# Primavera.net
KiCad netlist of a schematic drawn in Altium Designer
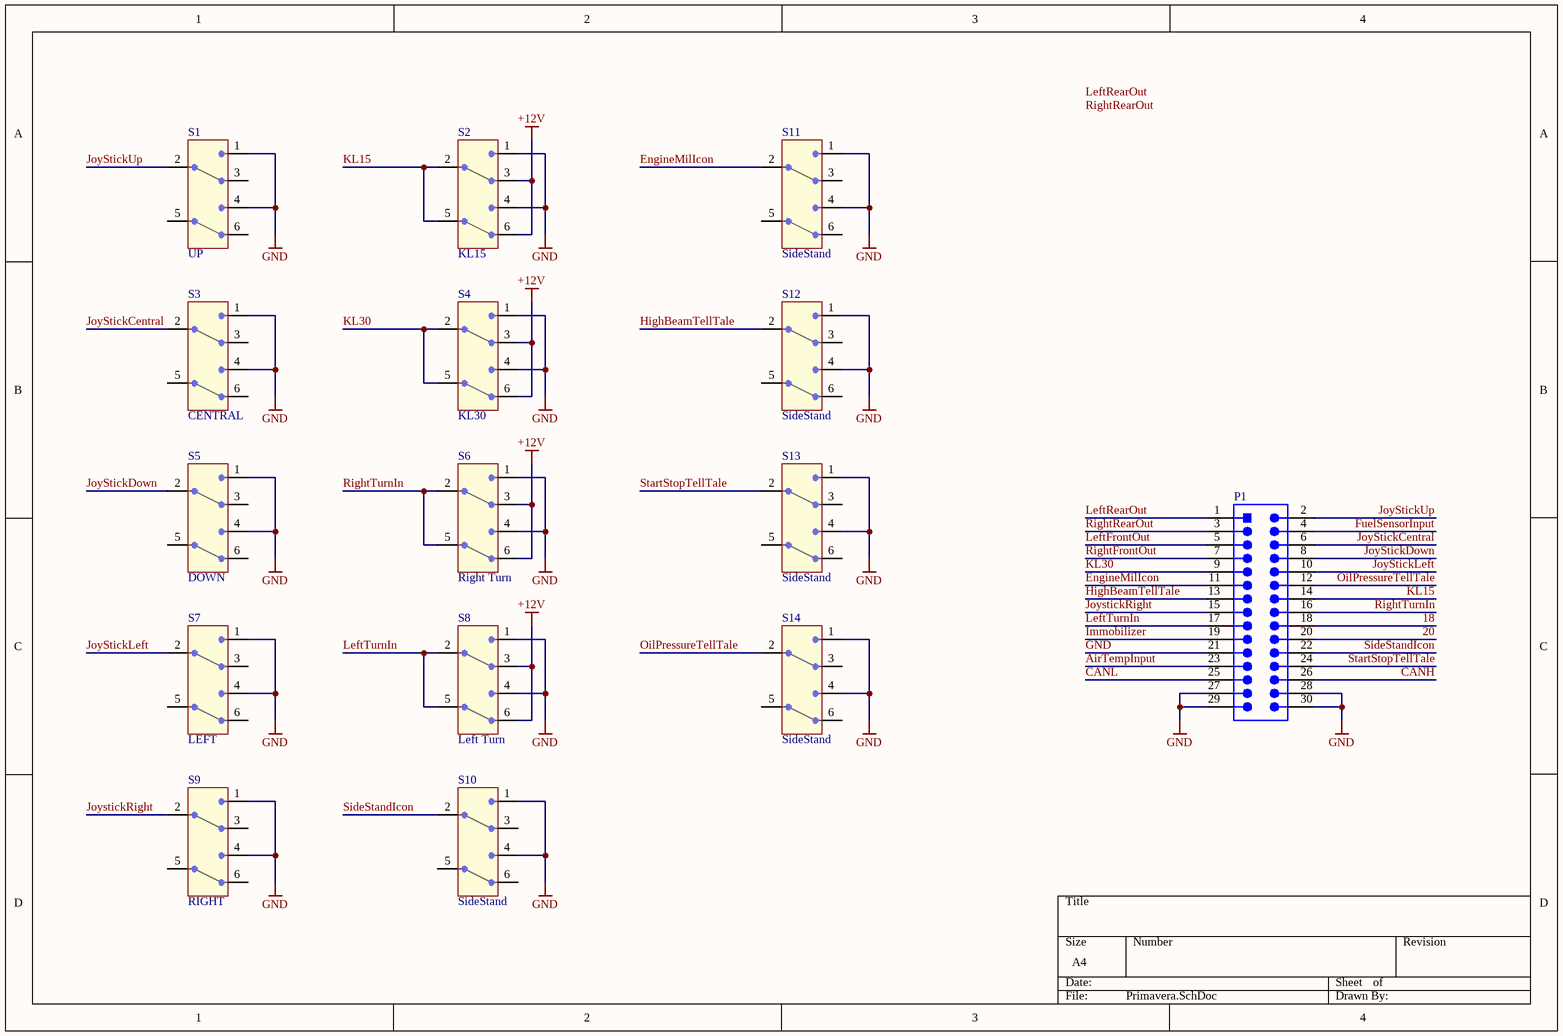
[diagram p0: Primavera.SchDoc]

(export (version "E")
  (design (tool "Eeschema 10.0.6"))
  (components
    (comp (ref "P1")
      (value "_30")
      (footprint "61203421721 - 30pole")
      (description "WR-BHD Box Header with short lever, Male, pitch 2.54mm, THT, Right Angle, 30p")
      (fields
        (field (name "MANUFACTURER") "Wurth Elektronik")
        (field (name "MANUFACTURER PART NUMBER") "61202622121")
      )
      (libsource (lib "Altium_WR-BHD (rev22a)") (part "61202622121_30"))
    )
    (comp (ref "S1")
      (value "UP")
      (footprint "8.5x8.5_DPDT")
      (libsource (lib "Switches") (part "8.5x8.5_DPDT"))
    )
    (comp (ref "S2")
      (value "KL15")
      (footprint "8.5x8.5_DPDT")
      (libsource (lib "Switches") (part "8.5x8.5_DPDT"))
    )
    (comp (ref "S3")
      (value "CENTRAL")
      (footprint "8.5x8.5_DPDT")
      (libsource (lib "Switches") (part "8.5x8.5_DPDT"))
    )
    (comp (ref "S4")
      (value "KL30")
      (footprint "8.5x8.5_DPDT")
      (libsource (lib "Switches") (part "8.5x8.5_DPDT"))
    )
    (comp (ref "S5")
      (value "DOWN")
      (footprint "8.5x8.5_DPDT")
      (libsource (lib "Switches") (part "8.5x8.5_DPDT"))
    )
    (comp (ref "S6")
      (value "Right Turn")
      (footprint "8.5x8.5_DPDT")
      (libsource (lib "Switches") (part "8.5x8.5_DPDT"))
    )
    (comp (ref "S7")
      (value "LEFT")
      (footprint "8.5x8.5_DPDT")
      (libsource (lib "Switches") (part "8.5x8.5_DPDT"))
    )
    (comp (ref "S8")
      (value "Left Turn")
      (footprint "8.5x8.5_DPDT")
      (libsource (lib "Switches") (part "8.5x8.5_DPDT"))
    )
    (comp (ref "S9")
      (value "RIGHT")
      (footprint "8.5x8.5_DPDT")
      (libsource (lib "Switches") (part "8.5x8.5_DPDT"))
    )
    (comp (ref "S10")
      (value "SideStand")
      (footprint "8.5x8.5_DPDT")
      (libsource (lib "Switches") (part "8.5x8.5_DPDT"))
    )
    (comp (ref "S11")
      (value "SideStand")
      (footprint "8.5x8.5_DPDT")
      (libsource (lib "Switches") (part "8.5x8.5_DPDT"))
    )
    (comp (ref "S12")
      (value "SideStand")
      (footprint "8.5x8.5_DPDT")
      (libsource (lib "Switches") (part "8.5x8.5_DPDT"))
    )
    (comp (ref "S13")
      (value "SideStand")
      (footprint "8.5x8.5_DPDT")
      (libsource (lib "Switches") (part "8.5x8.5_DPDT"))
    )
    (comp (ref "S14")
      (value "SideStand")
      (footprint "8.5x8.5_DPDT")
      (libsource (lib "Switches") (part "8.5x8.5_DPDT"))
    )
  )
  (nets
    (net (code "1") (name "+12V") (class "Default")
      (node (ref "S2") (pin "3") (pinfunction "3_3") (pintype "passive"))
      (node (ref "S2") (pin "6") (pinfunction "6_6") (pintype "passive"))
      (node (ref "S4") (pin "3") (pinfunction "3_3") (pintype "passive"))
      (node (ref "S4") (pin "6") (pinfunction "6_6") (pintype "passive"))
      (node (ref "S6") (pin "3") (pinfunction "3_3") (pintype "passive"))
      (node (ref "S6") (pin "6") (pinfunction "6_6") (pintype "passive"))
      (node (ref "S8") (pin "3") (pinfunction "3_3") (pintype "passive"))
      (node (ref "S8") (pin "6") (pinfunction "6_6") (pintype "passive"))
    )
    (net (code "2") (name "/18") (class "Default")
      (node (ref "P1") (pin "18") (pinfunction "18_18") (pintype "passive"))
    )
    (net (code "3") (name "/20") (class "Default")
      (node (ref "P1") (pin "20") (pinfunction "20_20") (pintype "passive"))
    )
    (net (code "4") (name "/AirTempInput") (class "Default")
      (node (ref "P1") (pin "23") (pinfunction "23_23") (pintype "passive"))
    )
    (net (code "5") (name "/CANH") (class "Default")
      (node (ref "P1") (pin "26") (pinfunction "26_26") (pintype "passive"))
    )
    (net (code "6") (name "/CANL") (class "Default")
      (node (ref "P1") (pin "25") (pinfunction "25_25") (pintype "passive"))
    )
    (net (code "7") (name "/EngineMilIcon") (class "Default")
      (node (ref "P1") (pin "11") (pinfunction "11_11") (pintype "passive"))
      (node (ref "S11") (pin "2") (pinfunction "2_2") (pintype "passive"))
    )
    (net (code "8") (name "/FuelSensorInput") (class "Default")
      (node (ref "P1") (pin "4") (pinfunction "4_4") (pintype "passive"))
    )
    (net (code "9") (name "/HighBeamTellTale") (class "Default")
      (node (ref "P1") (pin "13") (pinfunction "13_13") (pintype "passive"))
      (node (ref "S12") (pin "2") (pinfunction "2_2") (pintype "passive"))
    )
    (net (code "10") (name "/Immobilizer") (class "Default")
      (node (ref "P1") (pin "19") (pinfunction "19_19") (pintype "passive"))
    )
    (net (code "11") (name "/JoyStickCentral") (class "Default")
      (node (ref "P1") (pin "6") (pinfunction "6_6") (pintype "passive"))
      (node (ref "S3") (pin "2") (pinfunction "2_2") (pintype "passive"))
    )
    (net (code "12") (name "/JoyStickDown") (class "Default")
      (node (ref "P1") (pin "8") (pinfunction "8_8") (pintype "passive"))
      (node (ref "S5") (pin "2") (pinfunction "2_2") (pintype "passive"))
    )
    (net (code "13") (name "/JoyStickLeft") (class "Default")
      (node (ref "P1") (pin "10") (pinfunction "10_10") (pintype "passive"))
      (node (ref "S7") (pin "2") (pinfunction "2_2") (pintype "passive"))
    )
    (net (code "14") (name "/JoyStickUp") (class "Default")
      (node (ref "P1") (pin "2") (pinfunction "2_2") (pintype "passive"))
      (node (ref "S1") (pin "2") (pinfunction "2_2") (pintype "passive"))
    )
    (net (code "15") (name "/JoystickRight") (class "Default")
      (node (ref "P1") (pin "15") (pinfunction "15_15") (pintype "passive"))
      (node (ref "S9") (pin "2") (pinfunction "2_2") (pintype "passive"))
    )
    (net (code "16") (name "/KL15") (class "Default")
      (node (ref "P1") (pin "14") (pinfunction "14_14") (pintype "passive"))
      (node (ref "S2") (pin "2") (pinfunction "2_2") (pintype "passive"))
      (node (ref "S2") (pin "5") (pinfunction "5_5") (pintype "passive"))
    )
    (net (code "17") (name "/KL30") (class "Default")
      (node (ref "P1") (pin "9") (pinfunction "9_9") (pintype "passive"))
      (node (ref "S4") (pin "2") (pinfunction "2_2") (pintype "passive"))
      (node (ref "S4") (pin "5") (pinfunction "5_5") (pintype "passive"))
    )
    (net (code "18") (name "/LeftFrontOut") (class "Default")
      (node (ref "P1") (pin "5") (pinfunction "5_5") (pintype "passive"))
    )
    (net (code "19") (name "/LeftRearOut") (class "Default")
      (node (ref "P1") (pin "1") (pinfunction "1_1") (pintype "passive"))
    )
    (net (code "20") (name "/LeftTurnIn") (class "Default")
      (node (ref "P1") (pin "17") (pinfunction "17_17") (pintype "passive"))
      (node (ref "S8") (pin "2") (pinfunction "2_2") (pintype "passive"))
      (node (ref "S8") (pin "5") (pinfunction "5_5") (pintype "passive"))
    )
    (net (code "21") (name "/OilPressureTellTale") (class "Default")
      (node (ref "P1") (pin "12") (pinfunction "12_12") (pintype "passive"))
      (node (ref "S14") (pin "2") (pinfunction "2_2") (pintype "passive"))
    )
    (net (code "22") (name "/RightFrontOut") (class "Default")
      (node (ref "P1") (pin "7") (pinfunction "7_7") (pintype "passive"))
    )
    (net (code "23") (name "/RightRearOut") (class "Default")
      (node (ref "P1") (pin "3") (pinfunction "3_3") (pintype "passive"))
    )
    (net (code "24") (name "/RightTurnIn") (class "Default")
      (node (ref "P1") (pin "16") (pinfunction "16_16") (pintype "passive"))
      (node (ref "S6") (pin "2") (pinfunction "2_2") (pintype "passive"))
      (node (ref "S6") (pin "5") (pinfunction "5_5") (pintype "passive"))
    )
    (net (code "25") (name "/SideStandIcon") (class "Default")
      (node (ref "P1") (pin "22") (pinfunction "22_22") (pintype "passive"))
      (node (ref "S10") (pin "2") (pinfunction "2_2") (pintype "passive"))
    )
    (net (code "26") (name "/StartStopTellTale") (class "Default")
      (node (ref "P1") (pin "24") (pinfunction "24_24") (pintype "passive"))
      (node (ref "S13") (pin "2") (pinfunction "2_2") (pintype "passive"))
    )
    (net (code "27") (name "GND") (class "Default")
      (node (ref "P1") (pin "21") (pinfunction "21_21") (pintype "passive"))
      (node (ref "P1") (pin "27") (pinfunction "27_27") (pintype "passive"))
      (node (ref "P1") (pin "28") (pinfunction "28_28") (pintype "passive"))
      (node (ref "P1") (pin "29") (pinfunction "29_29") (pintype "passive"))
      (node (ref "P1") (pin "30") (pinfunction "30_30") (pintype "passive"))
      (node (ref "S1") (pin "1") (pinfunction "1_1") (pintype "passive"))
      (node (ref "S1") (pin "4") (pinfunction "4_4") (pintype "passive"))
      (node (ref "S10") (pin "1") (pinfunction "1_1") (pintype "passive"))
      (node (ref "S10") (pin "4") (pinfunction "4_4") (pintype "passive"))
      (node (ref "S11") (pin "1") (pinfunction "1_1") (pintype "passive"))
      (node (ref "S11") (pin "4") (pinfunction "4_4") (pintype "passive"))
      (node (ref "S12") (pin "1") (pinfunction "1_1") (pintype "passive"))
      (node (ref "S12") (pin "4") (pinfunction "4_4") (pintype "passive"))
      (node (ref "S13") (pin "1") (pinfunction "1_1") (pintype "passive"))
      (node (ref "S13") (pin "4") (pinfunction "4_4") (pintype "passive"))
      (node (ref "S14") (pin "1") (pinfunction "1_1") (pintype "passive"))
      (node (ref "S14") (pin "4") (pinfunction "4_4") (pintype "passive"))
      (node (ref "S2") (pin "1") (pinfunction "1_1") (pintype "passive"))
      (node (ref "S2") (pin "4") (pinfunction "4_4") (pintype "passive"))
      (node (ref "S3") (pin "1") (pinfunction "1_1") (pintype "passive"))
      (node (ref "S3") (pin "4") (pinfunction "4_4") (pintype "passive"))
      (node (ref "S4") (pin "1") (pinfunction "1_1") (pintype "passive"))
      (node (ref "S4") (pin "4") (pinfunction "4_4") (pintype "passive"))
      (node (ref "S5") (pin "1") (pinfunction "1_1") (pintype "passive"))
      (node (ref "S5") (pin "4") (pinfunction "4_4") (pintype "passive"))
      (node (ref "S6") (pin "1") (pinfunction "1_1") (pintype "passive"))
      (node (ref "S6") (pin "4") (pinfunction "4_4") (pintype "passive"))
      (node (ref "S7") (pin "1") (pinfunction "1_1") (pintype "passive"))
      (node (ref "S7") (pin "4") (pinfunction "4_4") (pintype "passive"))
      (node (ref "S8") (pin "1") (pinfunction "1_1") (pintype "passive"))
      (node (ref "S8") (pin "4") (pinfunction "4_4") (pintype "passive"))
      (node (ref "S9") (pin "1") (pinfunction "1_1") (pintype "passive"))
      (node (ref "S9") (pin "4") (pinfunction "4_4") (pintype "passive"))
    )
    (net (code "28") (name "unconnected-(S1-Pad3)") (class "Default")
      (node (ref "S1") (pin "3") (pinfunction "3_3") (pintype "passive"))
    )
    (net (code "29") (name "unconnected-(S1-Pad5)") (class "Default")
      (node (ref "S1") (pin "5") (pinfunction "5_5") (pintype "passive"))
    )
    (net (code "30") (name "unconnected-(S1-Pad6)") (class "Default")
      (node (ref "S1") (pin "6") (pinfunction "6_6") (pintype "passive"))
    )
    (net (code "31") (name "unconnected-(S3-Pad3)") (class "Default")
      (node (ref "S3") (pin "3") (pinfunction "3_3") (pintype "passive"))
    )
    (net (code "32") (name "unconnected-(S3-Pad5)") (class "Default")
      (node (ref "S3") (pin "5") (pinfunction "5_5") (pintype "passive"))
    )
    (net (code "33") (name "unconnected-(S3-Pad6)") (class "Default")
      (node (ref "S3") (pin "6") (pinfunction "6_6") (pintype "passive"))
    )
    (net (code "34") (name "unconnected-(S5-Pad3)") (class "Default")
      (node (ref "S5") (pin "3") (pinfunction "3_3") (pintype "passive"))
    )
    (net (code "35") (name "unconnected-(S5-Pad5)") (class "Default")
      (node (ref "S5") (pin "5") (pinfunction "5_5") (pintype "passive"))
    )
    (net (code "36") (name "unconnected-(S5-Pad6)") (class "Default")
      (node (ref "S5") (pin "6") (pinfunction "6_6") (pintype "passive"))
    )
    (net (code "37") (name "unconnected-(S7-Pad3)") (class "Default")
      (node (ref "S7") (pin "3") (pinfunction "3_3") (pintype "passive"))
    )
    (net (code "38") (name "unconnected-(S7-Pad5)") (class "Default")
      (node (ref "S7") (pin "5") (pinfunction "5_5") (pintype "passive"))
    )
    (net (code "39") (name "unconnected-(S7-Pad6)") (class "Default")
      (node (ref "S7") (pin "6") (pinfunction "6_6") (pintype "passive"))
    )
    (net (code "40") (name "unconnected-(S9-Pad3)") (class "Default")
      (node (ref "S9") (pin "3") (pinfunction "3_3") (pintype "passive"))
    )
    (net (code "41") (name "unconnected-(S9-Pad5)") (class "Default")
      (node (ref "S9") (pin "5") (pinfunction "5_5") (pintype "passive"))
    )
    (net (code "42") (name "unconnected-(S9-Pad6)") (class "Default")
      (node (ref "S9") (pin "6") (pinfunction "6_6") (pintype "passive"))
    )
    (net (code "43") (name "unconnected-(S10-Pad3)") (class "Default")
      (node (ref "S10") (pin "3") (pinfunction "3_3") (pintype "passive"))
    )
    (net (code "44") (name "unconnected-(S10-Pad5)") (class "Default")
      (node (ref "S10") (pin "5") (pinfunction "5_5") (pintype "passive"))
    )
    (net (code "45") (name "unconnected-(S10-Pad6)") (class "Default")
      (node (ref "S10") (pin "6") (pinfunction "6_6") (pintype "passive"))
    )
    (net (code "46") (name "unconnected-(S11-Pad3)") (class "Default")
      (node (ref "S11") (pin "3") (pinfunction "3_3") (pintype "passive"))
    )
    (net (code "47") (name "unconnected-(S11-Pad5)") (class "Default")
      (node (ref "S11") (pin "5") (pinfunction "5_5") (pintype "passive"))
    )
    (net (code "48") (name "unconnected-(S11-Pad6)") (class "Default")
      (node (ref "S11") (pin "6") (pinfunction "6_6") (pintype "passive"))
    )
    (net (code "49") (name "unconnected-(S12-Pad3)") (class "Default")
      (node (ref "S12") (pin "3") (pinfunction "3_3") (pintype "passive"))
    )
    (net (code "50") (name "unconnected-(S12-Pad5)") (class "Default")
      (node (ref "S12") (pin "5") (pinfunction "5_5") (pintype "passive"))
    )
    (net (code "51") (name "unconnected-(S12-Pad6)") (class "Default")
      (node (ref "S12") (pin "6") (pinfunction "6_6") (pintype "passive"))
    )
    (net (code "52") (name "unconnected-(S13-Pad3)") (class "Default")
      (node (ref "S13") (pin "3") (pinfunction "3_3") (pintype "passive"))
    )
    (net (code "53") (name "unconnected-(S13-Pad5)") (class "Default")
      (node (ref "S13") (pin "5") (pinfunction "5_5") (pintype "passive"))
    )
    (net (code "54") (name "unconnected-(S13-Pad6)") (class "Default")
      (node (ref "S13") (pin "6") (pinfunction "6_6") (pintype "passive"))
    )
    (net (code "55") (name "unconnected-(S14-Pad3)") (class "Default")
      (node (ref "S14") (pin "3") (pinfunction "3_3") (pintype "passive"))
    )
    (net (code "56") (name "unconnected-(S14-Pad5)") (class "Default")
      (node (ref "S14") (pin "5") (pinfunction "5_5") (pintype "passive"))
    )
    (net (code "57") (name "unconnected-(S14-Pad6)") (class "Default")
      (node (ref "S14") (pin "6") (pinfunction "6_6") (pintype "passive"))
    )
  )
)
